# basic_nmea_wifi_2021-01-28.net
KiCad netlist of a schematic drawn in EasyEDA
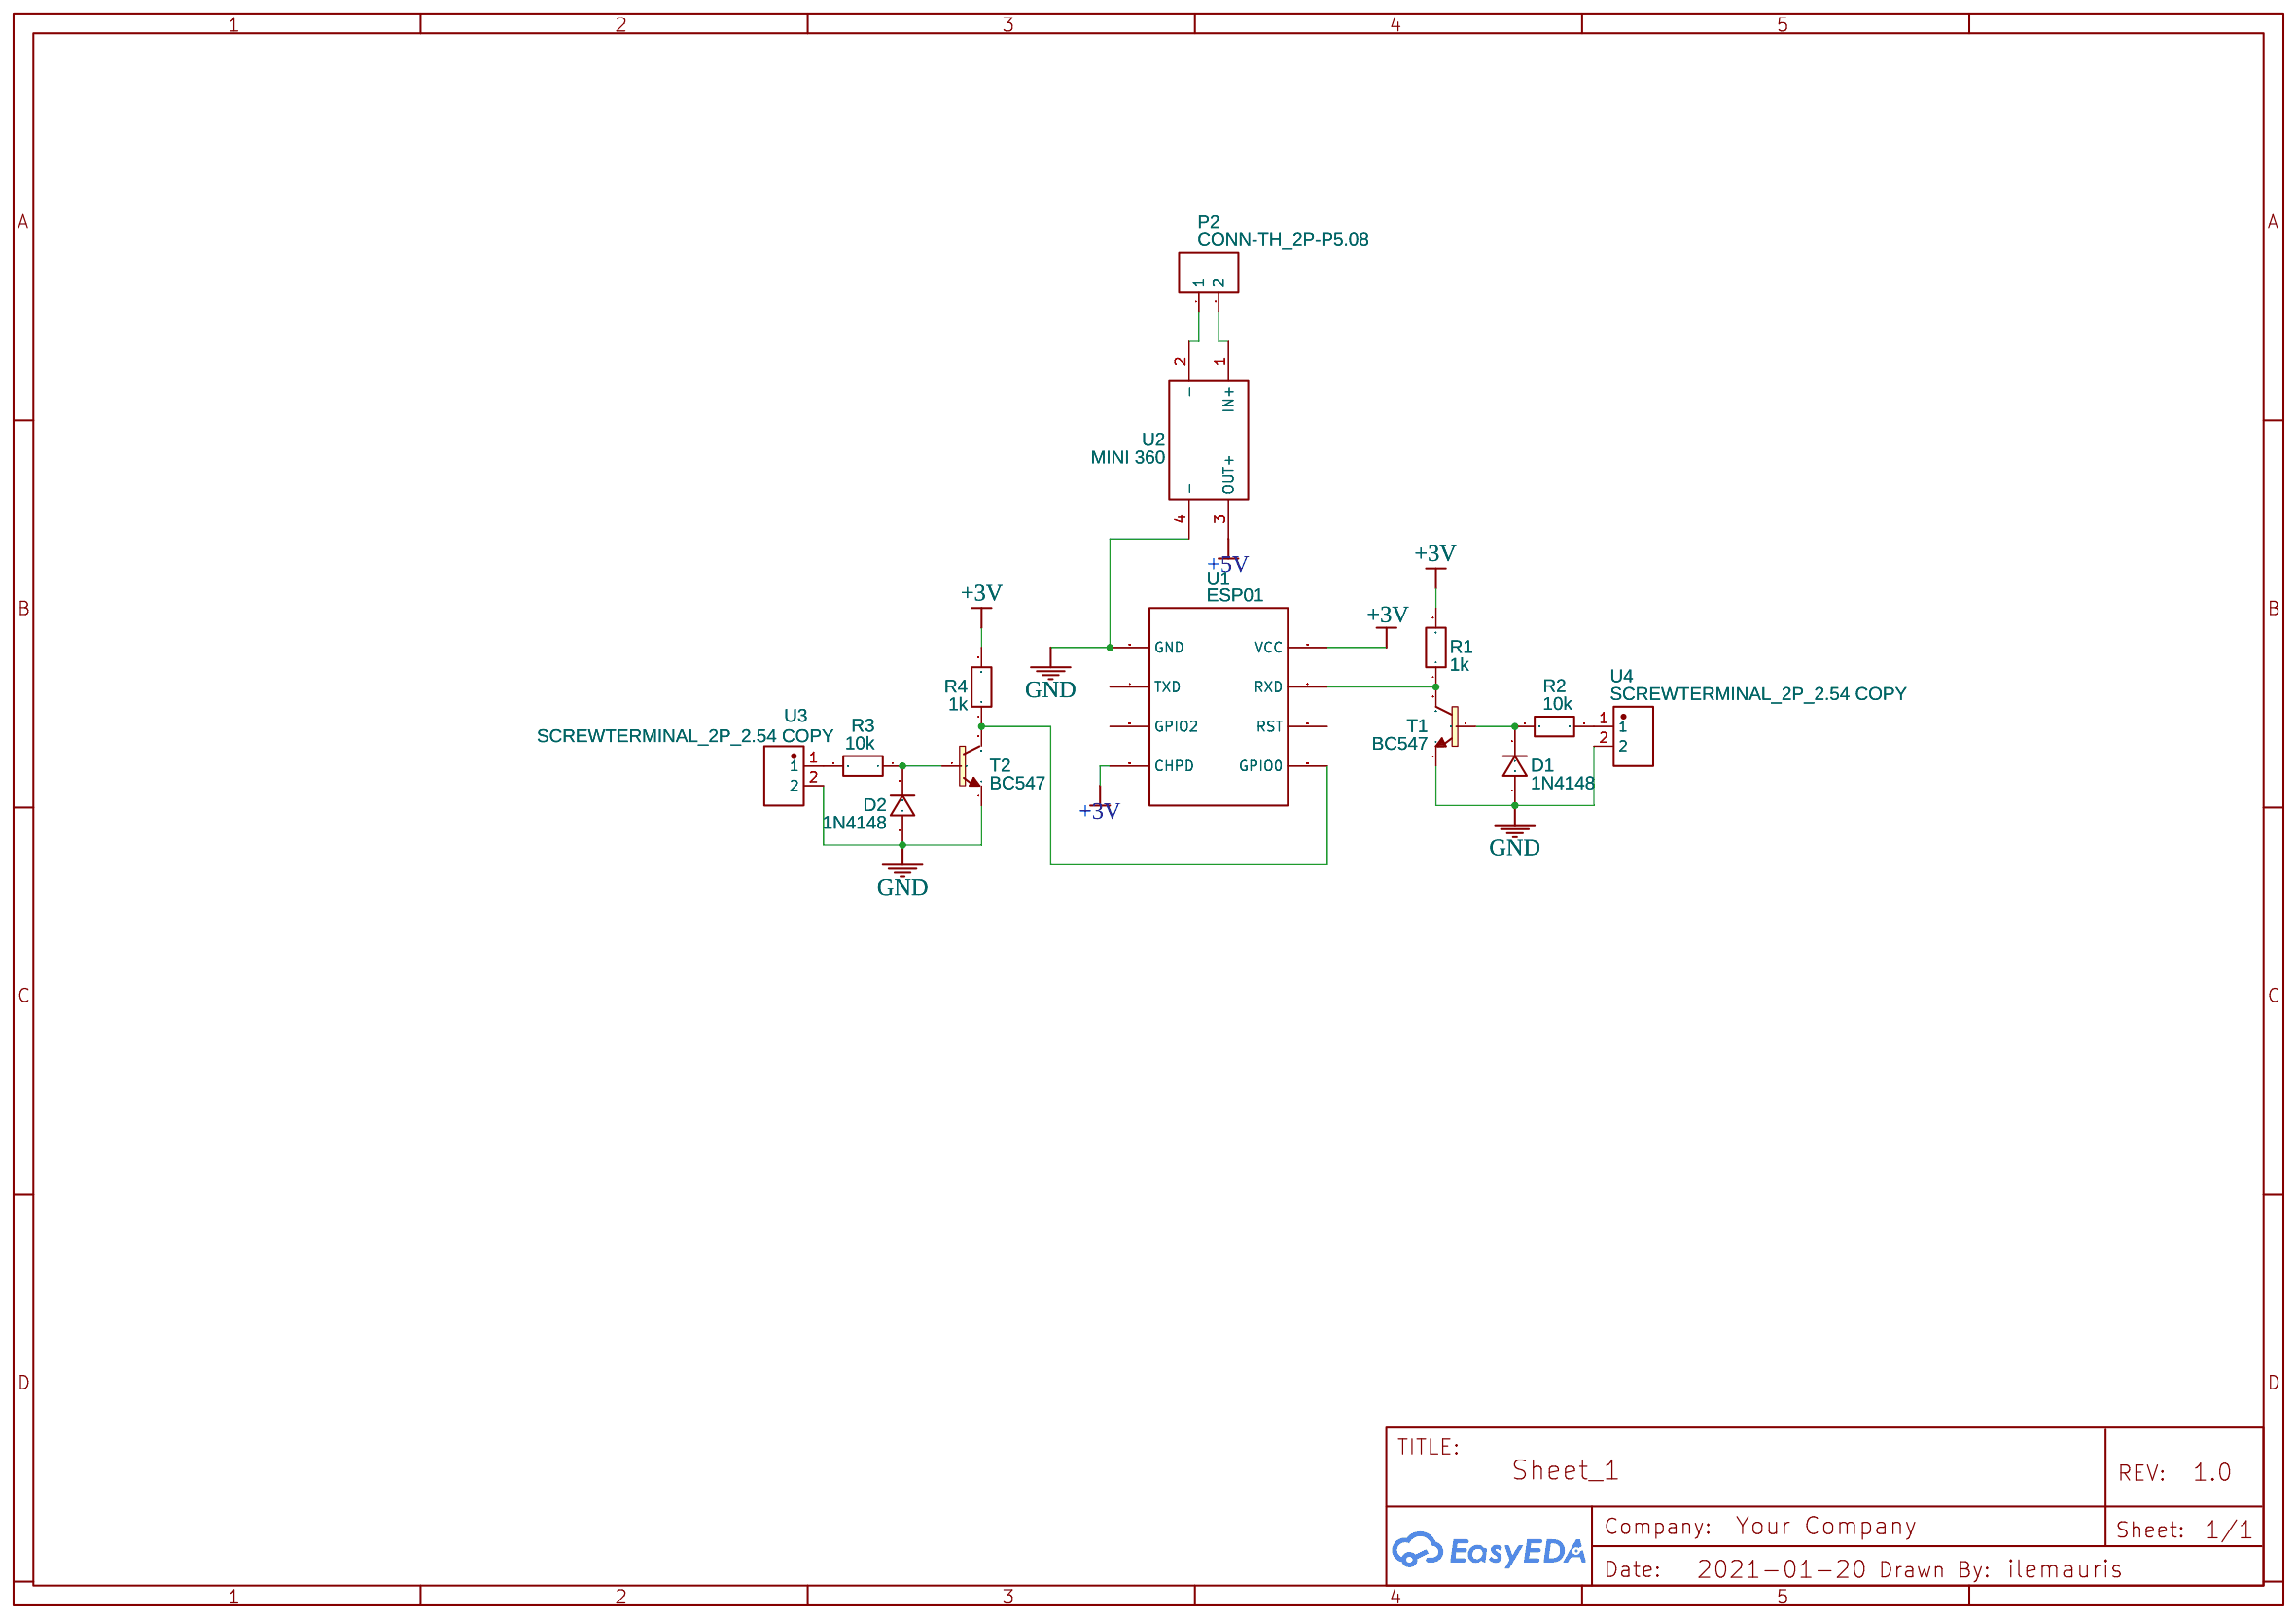
[diagram p0: schematic sheet]

(export (version "E")
  (design (tool "Eeschema 10.0.6"))
  (components
    (comp (ref "D1")
      (value "1N4148")
      (fields (field (name "BOM_Supplier Part") "C14516"))
      (libsource (lib "") (part "1N4148_1"))
    )
    (comp (ref "D2")
      (value "1N4148")
      (fields (field (name "BOM_Supplier Part") "C14516"))
      (libsource (lib "") (part "1N4148"))
    )
    (comp (ref "P2") (value "CONN-TH_2P-P5.08") (libsource (lib "") (part "CONN-TH_2P-P5.08")))
    (comp (ref "R1") (value "1k") (libsource (lib "") (part "R_AXIAL-0.3_EU_2")))
    (comp (ref "R2") (value "10k") (libsource (lib "") (part "R_AXIAL-0.3_EU")))
    (comp (ref "R3") (value "10k") (libsource (lib "") (part "R_AXIAL-0.3_EU_1")))
    (comp (ref "R4") (value "1k") (libsource (lib "") (part "R_AXIAL-0.3_EU_2")))
    (comp (ref "T1") (value "BC547") (libsource (lib "") (part "BC547_1")))
    (comp (ref "T2") (value "BC547") (libsource (lib "") (part "BC547")))
    (comp (ref "U1")
      (value "ESP01")
      (fields (field (name "BOM_Manufacturer Part") "Espressif"))
      (libsource (lib "") (part "ESP01"))
    )
    (comp (ref "U2") (value "MINI 360") (libsource (lib "") (part "MINI 360")))
    (comp (ref "U3")
      (value "SCREWTERMINAL_2P_2.54 COPY")
      (fields
        (field (name "BOM_Manufacturer Part") "DG308-2.54-02P-14-00A(H)")
        (field (name "BOM_Supplier Part") "DG308 2,54-2")
      )
      (libsource (lib "") (part "SCREWTERMINAL_2P_2.54 COPY"))
    )
    (comp (ref "U4")
      (value "SCREWTERMINAL_2P_2.54 COPY")
      (fields
        (field (name "BOM_Manufacturer Part") "DG308-2.54-02P-14-00A(H)")
        (field (name "BOM_Supplier Part") "DG308 2,54-2")
      )
      (libsource (lib "") (part "SCREWTERMINAL_2P_2.54 COPY_1"))
    )
  )
  (nets
    (net (code "1") (name "+3V") (class "Default")
      (node (ref "R1") (pin "2") (pinfunction "2_2") (pintype "unspecified"))
      (node (ref "R4") (pin "2") (pinfunction "2_2") (pintype "unspecified"))
      (node (ref "U1") (pin "CH_PD") (pinfunction "CHPD_CH_PD") (pintype "unspecified"))
      (node (ref "U1") (pin "VCC") (pinfunction "VCC_VCC") (pintype "unspecified"))
    )
    (net (code "2") (name "+5V") (class "Default")
      (node (ref "U2") (pin "3") (pinfunction "OUT+_3") (pintype "unspecified"))
    )
    (net (code "3") (name "GND") (class "Default")
      (node (ref "D1") (pin "1") (pinfunction "1_1") (pintype "unspecified"))
      (node (ref "D2") (pin "1") (pinfunction "1_1") (pintype "unspecified"))
      (node (ref "T1") (pin "1") (pinfunction "E_1") (pintype "bidirectional"))
      (node (ref "T2") (pin "1") (pinfunction "E_1") (pintype "bidirectional"))
      (node (ref "U1") (pin "GND") (pinfunction "GND_GND") (pintype "unspecified"))
      (node (ref "U2") (pin "4") (pinfunction "-_4") (pintype "unspecified"))
      (node (ref "U3") (pin "2") (pinfunction "2_2") (pintype "unspecified"))
      (node (ref "U4") (pin "2") (pinfunction "2_2") (pintype "unspecified"))
    )
    (net (code "4") (name "Net-(P2-Pad1)") (class "Default")
      (node (ref "P2") (pin "1") (pinfunction "1_1") (pintype "unspecified"))
      (node (ref "U2") (pin "2") (pinfunction "-_2") (pintype "unspecified"))
    )
    (net (code "5") (name "Net-(R2-Pad2)") (class "Default")
      (node (ref "R2") (pin "2") (pinfunction "2_2") (pintype "unspecified"))
      (node (ref "U4") (pin "1") (pinfunction "1_1") (pintype "unspecified"))
    )
    (net (code "6") (name "Net-(R3-Pad2)") (class "Default")
      (node (ref "R3") (pin "2") (pinfunction "2_2") (pintype "unspecified"))
      (node (ref "U3") (pin "1") (pinfunction "1_1") (pintype "unspecified"))
    )
    (net (code "7") (name "Net-(T1-B)") (class "Default")
      (node (ref "D1") (pin "2") (pinfunction "2_2") (pintype "unspecified"))
      (node (ref "R2") (pin "1") (pinfunction "1_1") (pintype "unspecified"))
      (node (ref "T1") (pin "2") (pinfunction "B_2") (pintype "bidirectional"))
    )
    (net (code "8") (name "Net-(T1-C)") (class "Default")
      (node (ref "R1") (pin "1") (pinfunction "1_1") (pintype "unspecified"))
      (node (ref "T1") (pin "3") (pinfunction "C_3") (pintype "bidirectional"))
      (node (ref "U1") (pin "RX") (pinfunction "RXD_RX") (pintype "unspecified"))
    )
    (net (code "9") (name "Net-(T2-B)") (class "Default")
      (node (ref "D2") (pin "2") (pinfunction "2_2") (pintype "unspecified"))
      (node (ref "R3") (pin "1") (pinfunction "1_1") (pintype "unspecified"))
      (node (ref "T2") (pin "2") (pinfunction "B_2") (pintype "bidirectional"))
    )
    (net (code "10") (name "Net-(T2-C)") (class "Default")
      (node (ref "R4") (pin "1") (pinfunction "1_1") (pintype "unspecified"))
      (node (ref "T2") (pin "3") (pinfunction "C_3") (pintype "bidirectional"))
      (node (ref "U1") (pin "GPIO0") (pinfunction "GPIO0_GPIO0") (pintype "unspecified"))
    )
    (net (code "11") (name "Net-(U2-IN+)") (class "Default")
      (node (ref "P2") (pin "2") (pinfunction "2_2") (pintype "unspecified"))
      (node (ref "U2") (pin "1") (pinfunction "IN+_1") (pintype "unspecified"))
    )
    (net (code "12") (name "unconnected-(U1-PadGPIO2)") (class "Default")
      (node (ref "U1") (pin "GPIO2") (pinfunction "GPIO2_GPIO2") (pintype "unspecified"))
    )
    (net (code "13") (name "unconnected-(U1-PadRST)") (class "Default")
      (node (ref "U1") (pin "RST") (pinfunction "RST_RST") (pintype "unspecified"))
    )
    (net (code "14") (name "unconnected-(U1-TXD-PadTX)") (class "Default")
      (node (ref "U1") (pin "TX") (pinfunction "TXD_TX") (pintype "unspecified"))
    )
  )
)
